# LINKER.net
KiCad netlist of a schematic drawn in Altium Designer
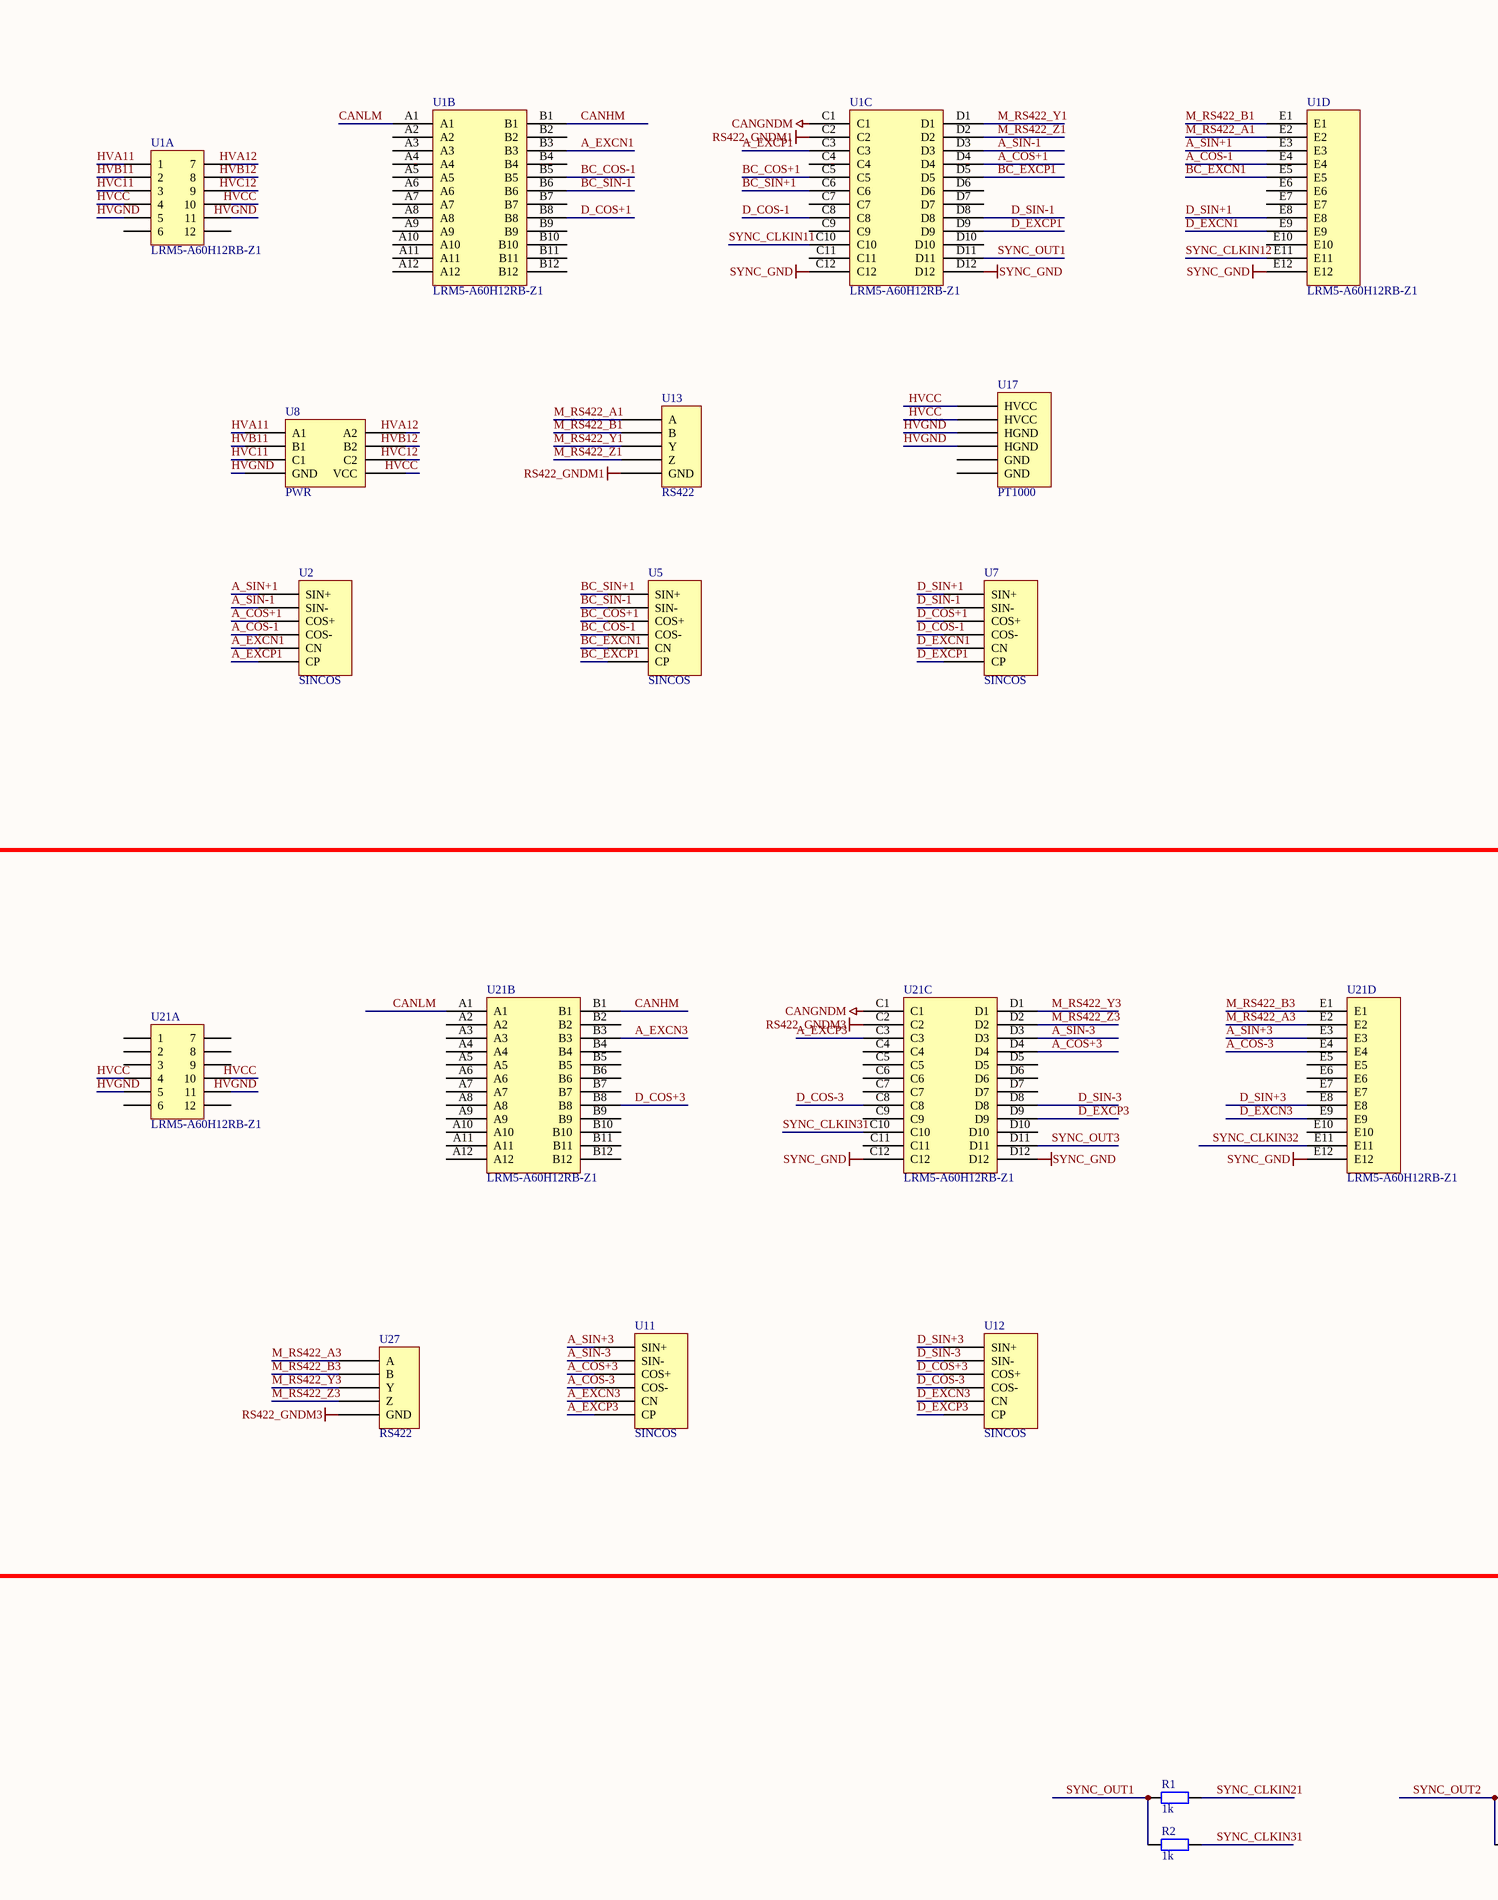
[diagram p0: LINKER.SchDoc, left]
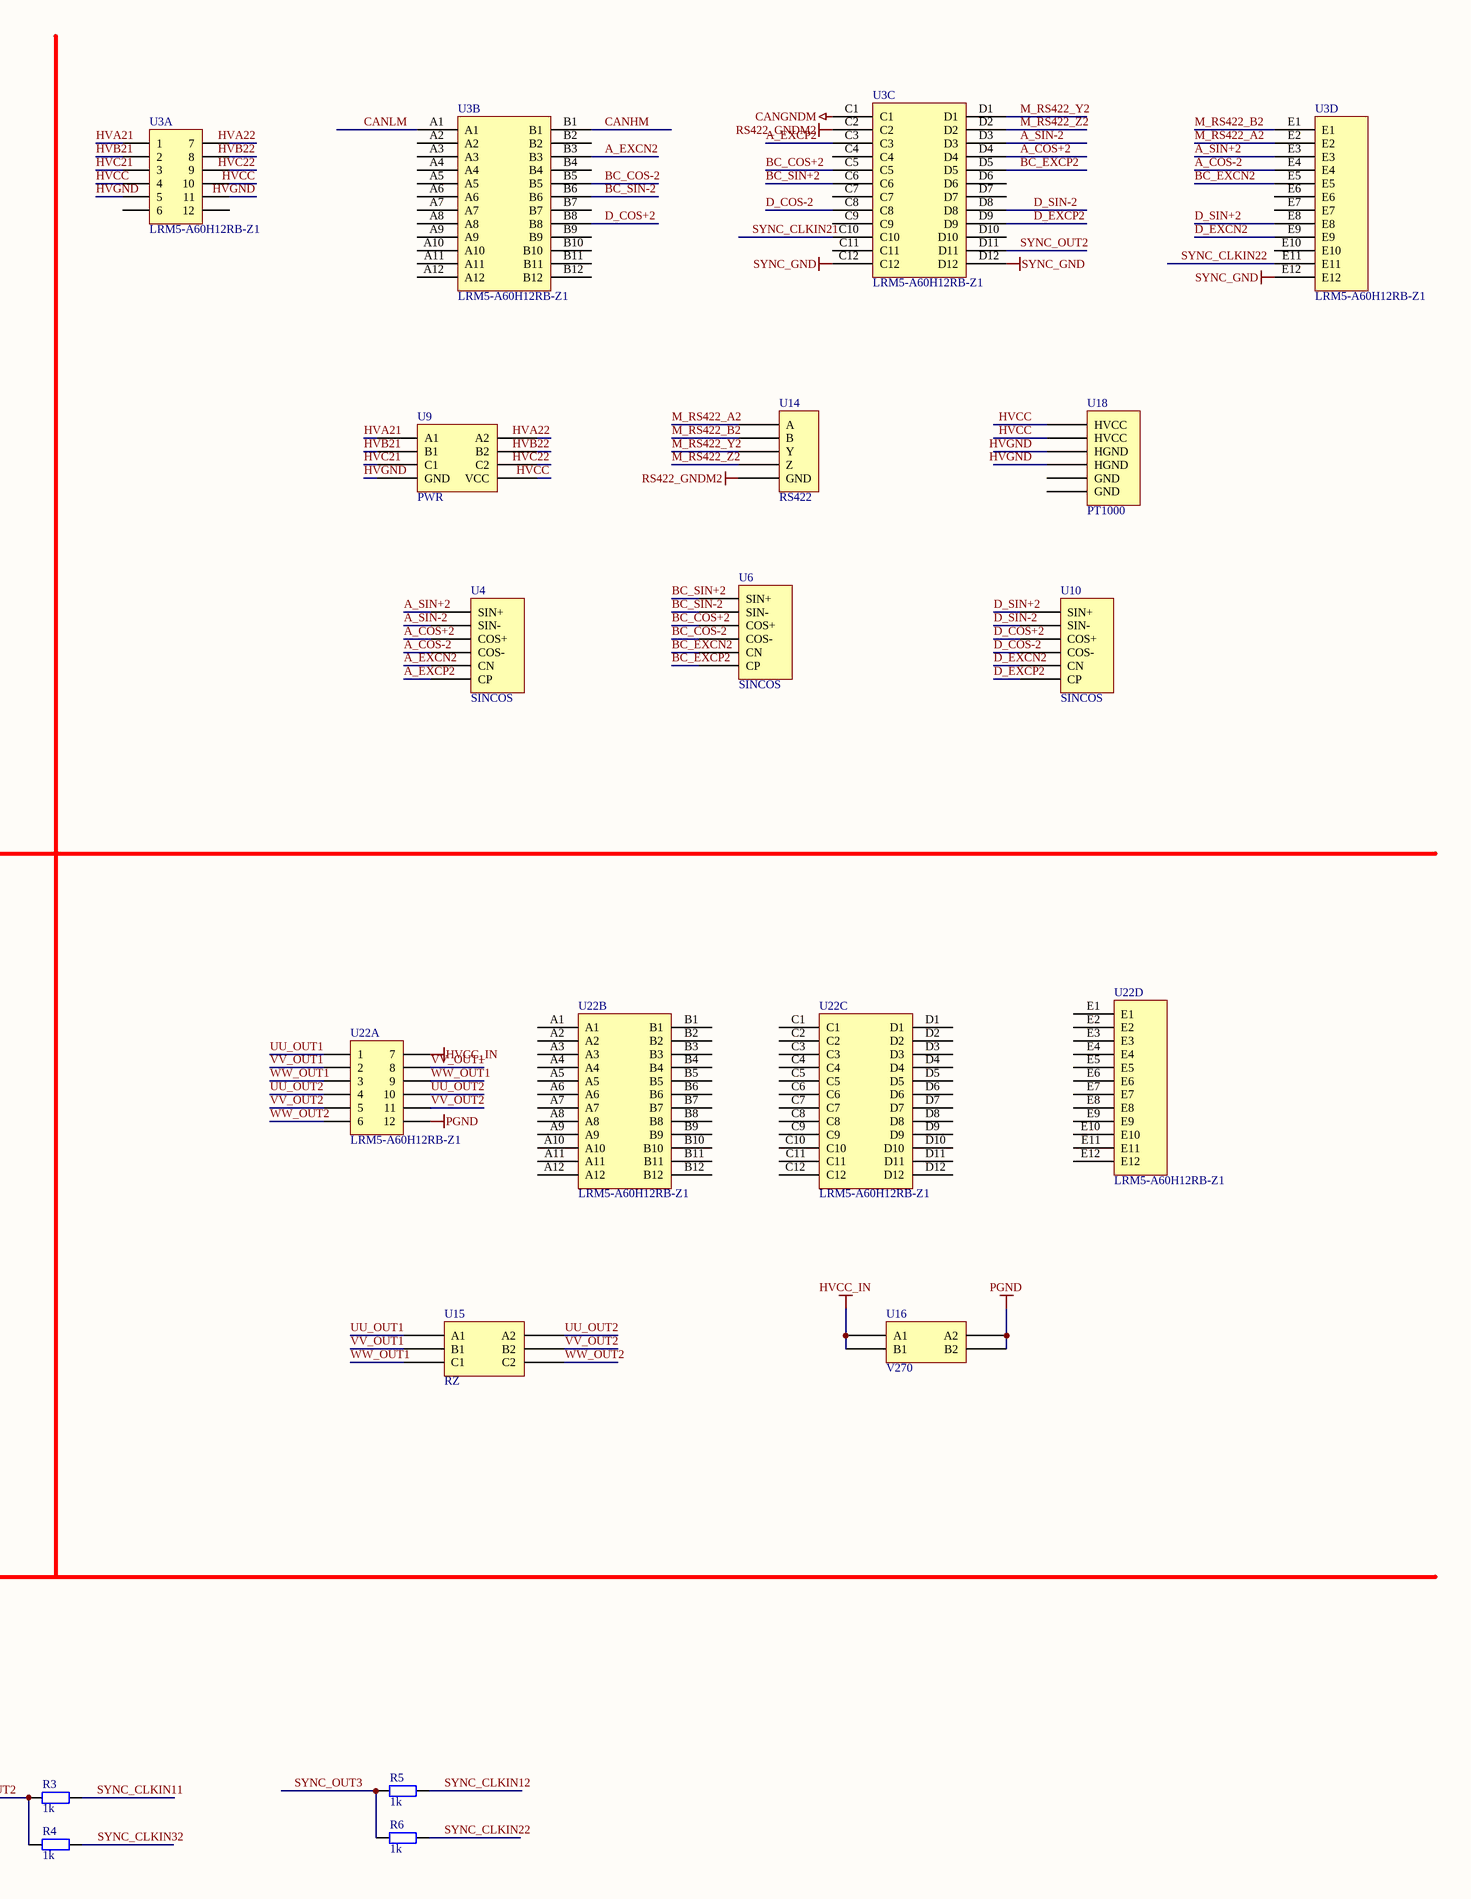
[diagram p1: LINKER.SchDoc, right]

(export (version "E")
  (design (tool "Eeschema 10.0.6"))
  (components
    (comp (ref "R1")
      (value "1k")
      (footprint "R1608-0603")
      (description "电阻器")
      (libsource (lib "电阻元件库") (part "RMK1608MB"))
    )
    (comp (ref "R2")
      (value "1k")
      (footprint "R1608-0603")
      (description "电阻器")
      (libsource (lib "电阻元件库") (part "RMK1608MB"))
    )
    (comp (ref "R3")
      (value "1k")
      (footprint "R1608-0603")
      (description "电阻器")
      (libsource (lib "电阻元件库") (part "RMK1608MB"))
    )
    (comp (ref "R4")
      (value "1k")
      (footprint "R1608-0603")
      (description "电阻器")
      (libsource (lib "电阻元件库") (part "RMK1608MB"))
    )
    (comp (ref "R5")
      (value "1k")
      (footprint "R1608-0603")
      (description "电阻器")
      (libsource (lib "电阻元件库") (part "RMK1608MB"))
    )
    (comp (ref "R6")
      (value "1k")
      (footprint "R1608-0603")
      (description "电阻器")
      (libsource (lib "电阻元件库") (part "RMK1608MB"))
    )
    (comp (ref "U1")
      (value "LRM5-A60H12RB-Z1")
      (footprint "LRM5-A60H12RB-Z1")
      (libsource (lib "Interface2") (part "MULTI_HEADER"))
    )
    (comp (ref "U2") (value "SINCOS") (footprint "SINCOS") (libsource (lib "link") (part "SINCOS")))
    (comp (ref "U3")
      (value "LRM5-A60H12RB-Z1")
      (footprint "LRM5-A60H12RB-Z1")
      (libsource (lib "Interface2") (part "MULTI_HEADER"))
    )
    (comp (ref "U4") (value "SINCOS") (footprint "SINCOS") (libsource (lib "link") (part "SINCOS")))
    (comp (ref "U5") (value "SINCOS") (footprint "SINCOS") (libsource (lib "link") (part "SINCOS")))
    (comp (ref "U6") (value "SINCOS") (footprint "SINCOS") (libsource (lib "link") (part "SINCOS")))
    (comp (ref "U7") (value "SINCOS") (footprint "SINCOS") (libsource (lib "link") (part "SINCOS")))
    (comp (ref "U8") (value "PWR") (footprint "PWR") (libsource (lib "link") (part "PWR")))
    (comp (ref "U9") (value "PWR") (footprint "PWR") (libsource (lib "link") (part "PWR")))
    (comp (ref "U10") (value "SINCOS") (footprint "SINCOS") (libsource (lib "link") (part "SINCOS")))
    (comp (ref "U11") (value "SINCOS") (footprint "SINCOS") (libsource (lib "link") (part "SINCOS")))
    (comp (ref "U12") (value "SINCOS") (footprint "SINCOS") (libsource (lib "link") (part "SINCOS")))
    (comp (ref "U13") (value "RS422") (footprint "RS422") (libsource (lib "link") (part "RS422")))
    (comp (ref "U14") (value "RS422") (footprint "RS422") (libsource (lib "link") (part "RS422")))
    (comp (ref "U15") (value "RZ") (footprint "RZ") (libsource (lib "link") (part "RZ")))
    (comp (ref "U16") (value "V270") (footprint "V270") (libsource (lib "link") (part "V270")))
    (comp (ref "U17") (value "PT1000") (footprint "PT1000") (libsource (lib "link") (part "PT1000")))
    (comp (ref "U18") (value "PT1000") (footprint "PT1000") (libsource (lib "link") (part "PT1000")))
    (comp (ref "U21")
      (value "LRM5-A60H12RB-Z1")
      (footprint "LRM5-A60H12RB-Z1")
      (libsource (lib "Interface2") (part "MULTI_HEADER"))
    )
    (comp (ref "U22")
      (value "LRM5-A60H12RB-Z1")
      (footprint "LRM5-A60H12RB-Z1")
      (libsource (lib "Interface2") (part "MULTI_HEADER"))
    )
    (comp (ref "U27") (value "RS422") (footprint "RS422") (libsource (lib "link") (part "RS422")))
  )
  (nets
    (net (code "1") (name "/A_COS+1") (class "Default")
      (node (ref "U1") (pin "D4") (pinfunction "D4_D4") (pintype "passive"))
      (node (ref "U2") (pin "3") (pinfunction "COS+_3") (pintype "passive"))
    )
    (net (code "2") (name "/A_COS+2") (class "Default")
      (node (ref "U3") (pin "D4") (pinfunction "D4_D4") (pintype "passive"))
      (node (ref "U4") (pin "3") (pinfunction "COS+_3") (pintype "passive"))
    )
    (net (code "3") (name "/A_COS+3") (class "Default")
      (node (ref "U11") (pin "3") (pinfunction "COS+_3") (pintype "passive"))
      (node (ref "U21") (pin "D4") (pinfunction "D4_D4") (pintype "passive"))
    )
    (net (code "4") (name "/A_COS-1") (class "Default")
      (node (ref "U1") (pin "E4") (pinfunction "E4_E4") (pintype "passive"))
      (node (ref "U2") (pin "4") (pinfunction "COS-_4") (pintype "passive"))
    )
    (net (code "5") (name "/A_COS-2") (class "Default")
      (node (ref "U3") (pin "E4") (pinfunction "E4_E4") (pintype "passive"))
      (node (ref "U4") (pin "4") (pinfunction "COS-_4") (pintype "passive"))
    )
    (net (code "6") (name "/A_COS-3") (class "Default")
      (node (ref "U11") (pin "4") (pinfunction "COS-_4") (pintype "passive"))
      (node (ref "U21") (pin "E4") (pinfunction "E4_E4") (pintype "passive"))
    )
    (net (code "7") (name "/A_EXCN1") (class "Default")
      (node (ref "U1") (pin "B3") (pinfunction "B3_B3") (pintype "passive"))
      (node (ref "U2") (pin "5") (pinfunction "CN_5") (pintype "passive"))
    )
    (net (code "8") (name "/A_EXCN2") (class "Default")
      (node (ref "U3") (pin "B3") (pinfunction "B3_B3") (pintype "passive"))
      (node (ref "U4") (pin "5") (pinfunction "CN_5") (pintype "passive"))
    )
    (net (code "9") (name "/A_EXCN3") (class "Default")
      (node (ref "U11") (pin "5") (pinfunction "CN_5") (pintype "passive"))
      (node (ref "U21") (pin "B3") (pinfunction "B3_B3") (pintype "passive"))
    )
    (net (code "10") (name "/A_EXCP1") (class "Default")
      (node (ref "U1") (pin "C3") (pinfunction "C3_C3") (pintype "passive"))
      (node (ref "U2") (pin "6") (pinfunction "CP_6") (pintype "passive"))
    )
    (net (code "11") (name "/A_EXCP2") (class "Default")
      (node (ref "U3") (pin "C3") (pinfunction "C3_C3") (pintype "passive"))
      (node (ref "U4") (pin "6") (pinfunction "CP_6") (pintype "passive"))
    )
    (net (code "12") (name "/A_EXCP3") (class "Default")
      (node (ref "U11") (pin "6") (pinfunction "CP_6") (pintype "passive"))
      (node (ref "U21") (pin "C3") (pinfunction "C3_C3") (pintype "passive"))
    )
    (net (code "13") (name "/A_SIN+1") (class "Default")
      (node (ref "U1") (pin "E3") (pinfunction "E3_E3") (pintype "passive"))
      (node (ref "U2") (pin "1") (pinfunction "SIN+_1") (pintype "passive"))
    )
    (net (code "14") (name "/A_SIN+2") (class "Default")
      (node (ref "U3") (pin "E3") (pinfunction "E3_E3") (pintype "passive"))
      (node (ref "U4") (pin "1") (pinfunction "SIN+_1") (pintype "passive"))
    )
    (net (code "15") (name "/A_SIN+3") (class "Default")
      (node (ref "U11") (pin "1") (pinfunction "SIN+_1") (pintype "passive"))
      (node (ref "U21") (pin "E3") (pinfunction "E3_E3") (pintype "passive"))
    )
    (net (code "16") (name "/A_SIN-1") (class "Default")
      (node (ref "U1") (pin "D3") (pinfunction "D3_D3") (pintype "passive"))
      (node (ref "U2") (pin "2") (pinfunction "SIN-_2") (pintype "passive"))
    )
    (net (code "17") (name "/A_SIN-2") (class "Default")
      (node (ref "U3") (pin "D3") (pinfunction "D3_D3") (pintype "passive"))
      (node (ref "U4") (pin "2") (pinfunction "SIN-_2") (pintype "passive"))
    )
    (net (code "18") (name "/A_SIN-3") (class "Default")
      (node (ref "U11") (pin "2") (pinfunction "SIN-_2") (pintype "passive"))
      (node (ref "U21") (pin "D3") (pinfunction "D3_D3") (pintype "passive"))
    )
    (net (code "19") (name "/BC_COS+1") (class "Default")
      (node (ref "U1") (pin "C5") (pinfunction "C5_C5") (pintype "passive"))
      (node (ref "U5") (pin "3") (pinfunction "COS+_3") (pintype "passive"))
    )
    (net (code "20") (name "/BC_COS+2") (class "Default")
      (node (ref "U3") (pin "C5") (pinfunction "C5_C5") (pintype "passive"))
      (node (ref "U6") (pin "3") (pinfunction "COS+_3") (pintype "passive"))
    )
    (net (code "21") (name "/BC_COS-1") (class "Default")
      (node (ref "U1") (pin "B5") (pinfunction "B5_B5") (pintype "passive"))
      (node (ref "U5") (pin "4") (pinfunction "COS-_4") (pintype "passive"))
    )
    (net (code "22") (name "/BC_COS-2") (class "Default")
      (node (ref "U3") (pin "B5") (pinfunction "B5_B5") (pintype "passive"))
      (node (ref "U6") (pin "4") (pinfunction "COS-_4") (pintype "passive"))
    )
    (net (code "23") (name "/BC_EXCN1") (class "Default")
      (node (ref "U1") (pin "E5") (pinfunction "E5_E5") (pintype "passive"))
      (node (ref "U5") (pin "5") (pinfunction "CN_5") (pintype "passive"))
    )
    (net (code "24") (name "/BC_EXCN2") (class "Default")
      (node (ref "U3") (pin "E5") (pinfunction "E5_E5") (pintype "passive"))
      (node (ref "U6") (pin "5") (pinfunction "CN_5") (pintype "passive"))
    )
    (net (code "25") (name "/BC_EXCP1") (class "Default")
      (node (ref "U1") (pin "D5") (pinfunction "D5_D5") (pintype "passive"))
      (node (ref "U5") (pin "6") (pinfunction "CP_6") (pintype "passive"))
    )
    (net (code "26") (name "/BC_EXCP2") (class "Default")
      (node (ref "U3") (pin "D5") (pinfunction "D5_D5") (pintype "passive"))
      (node (ref "U6") (pin "6") (pinfunction "CP_6") (pintype "passive"))
    )
    (net (code "27") (name "/BC_SIN+1") (class "Default")
      (node (ref "U1") (pin "C6") (pinfunction "C6_C6") (pintype "passive"))
      (node (ref "U5") (pin "1") (pinfunction "SIN+_1") (pintype "passive"))
    )
    (net (code "28") (name "/BC_SIN+2") (class "Default")
      (node (ref "U3") (pin "C6") (pinfunction "C6_C6") (pintype "passive"))
      (node (ref "U6") (pin "1") (pinfunction "SIN+_1") (pintype "passive"))
    )
    (net (code "29") (name "/BC_SIN-1") (class "Default")
      (node (ref "U1") (pin "B6") (pinfunction "B6_B6") (pintype "passive"))
      (node (ref "U5") (pin "2") (pinfunction "SIN-_2") (pintype "passive"))
    )
    (net (code "30") (name "/BC_SIN-2") (class "Default")
      (node (ref "U3") (pin "B6") (pinfunction "B6_B6") (pintype "passive"))
      (node (ref "U6") (pin "2") (pinfunction "SIN-_2") (pintype "passive"))
    )
    (net (code "31") (name "/CANHM") (class "Default")
      (node (ref "U1") (pin "B1") (pinfunction "B1_B1") (pintype "passive"))
      (node (ref "U21") (pin "B1") (pinfunction "B1_B1") (pintype "passive"))
      (node (ref "U3") (pin "B1") (pinfunction "B1_B1") (pintype "passive"))
    )
    (net (code "32") (name "/CANLM") (class "Default")
      (node (ref "U1") (pin "A1") (pinfunction "A1_A1") (pintype "passive"))
      (node (ref "U21") (pin "A1") (pinfunction "A1_A1") (pintype "passive"))
      (node (ref "U3") (pin "A1") (pinfunction "A1_A1") (pintype "passive"))
    )
    (net (code "33") (name "/D_COS+1") (class "Default")
      (node (ref "U1") (pin "B8") (pinfunction "B8_B8") (pintype "passive"))
      (node (ref "U7") (pin "3") (pinfunction "COS+_3") (pintype "passive"))
    )
    (net (code "34") (name "/D_COS+2") (class "Default")
      (node (ref "U10") (pin "3") (pinfunction "COS+_3") (pintype "passive"))
      (node (ref "U3") (pin "B8") (pinfunction "B8_B8") (pintype "passive"))
    )
    (net (code "35") (name "/D_COS+3") (class "Default")
      (node (ref "U12") (pin "3") (pinfunction "COS+_3") (pintype "passive"))
      (node (ref "U21") (pin "B8") (pinfunction "B8_B8") (pintype "passive"))
    )
    (net (code "36") (name "/D_COS-1") (class "Default")
      (node (ref "U1") (pin "C8") (pinfunction "C8_C8") (pintype "passive"))
      (node (ref "U7") (pin "4") (pinfunction "COS-_4") (pintype "passive"))
    )
    (net (code "37") (name "/D_COS-2") (class "Default")
      (node (ref "U10") (pin "4") (pinfunction "COS-_4") (pintype "passive"))
      (node (ref "U3") (pin "C8") (pinfunction "C8_C8") (pintype "passive"))
    )
    (net (code "38") (name "/D_COS-3") (class "Default")
      (node (ref "U12") (pin "4") (pinfunction "COS-_4") (pintype "passive"))
      (node (ref "U21") (pin "C8") (pinfunction "C8_C8") (pintype "passive"))
    )
    (net (code "39") (name "/D_EXCN1") (class "Default")
      (node (ref "U1") (pin "E9") (pinfunction "E9_E9") (pintype "passive"))
      (node (ref "U7") (pin "5") (pinfunction "CN_5") (pintype "passive"))
    )
    (net (code "40") (name "/D_EXCN2") (class "Default")
      (node (ref "U10") (pin "5") (pinfunction "CN_5") (pintype "passive"))
      (node (ref "U3") (pin "E9") (pinfunction "E9_E9") (pintype "passive"))
    )
    (net (code "41") (name "/D_EXCN3") (class "Default")
      (node (ref "U12") (pin "5") (pinfunction "CN_5") (pintype "passive"))
      (node (ref "U21") (pin "E9") (pinfunction "E9_E9") (pintype "passive"))
    )
    (net (code "42") (name "/D_EXCP1") (class "Default")
      (node (ref "U1") (pin "D9") (pinfunction "D9_D9") (pintype "passive"))
      (node (ref "U7") (pin "6") (pinfunction "CP_6") (pintype "passive"))
    )
    (net (code "43") (name "/D_EXCP2") (class "Default")
      (node (ref "U10") (pin "6") (pinfunction "CP_6") (pintype "passive"))
      (node (ref "U3") (pin "D9") (pinfunction "D9_D9") (pintype "passive"))
    )
    (net (code "44") (name "/D_EXCP3") (class "Default")
      (node (ref "U12") (pin "6") (pinfunction "CP_6") (pintype "passive"))
      (node (ref "U21") (pin "D9") (pinfunction "D9_D9") (pintype "passive"))
    )
    (net (code "45") (name "/D_SIN+1") (class "Default")
      (node (ref "U1") (pin "E8") (pinfunction "E8_E8") (pintype "passive"))
      (node (ref "U7") (pin "1") (pinfunction "SIN+_1") (pintype "passive"))
    )
    (net (code "46") (name "/D_SIN+2") (class "Default")
      (node (ref "U10") (pin "1") (pinfunction "SIN+_1") (pintype "passive"))
      (node (ref "U3") (pin "E8") (pinfunction "E8_E8") (pintype "passive"))
    )
    (net (code "47") (name "/D_SIN+3") (class "Default")
      (node (ref "U12") (pin "1") (pinfunction "SIN+_1") (pintype "passive"))
      (node (ref "U21") (pin "E8") (pinfunction "E8_E8") (pintype "passive"))
    )
    (net (code "48") (name "/D_SIN-1") (class "Default")
      (node (ref "U1") (pin "D8") (pinfunction "D8_D8") (pintype "passive"))
      (node (ref "U7") (pin "2") (pinfunction "SIN-_2") (pintype "passive"))
    )
    (net (code "49") (name "/D_SIN-2") (class "Default")
      (node (ref "U10") (pin "2") (pinfunction "SIN-_2") (pintype "passive"))
      (node (ref "U3") (pin "D8") (pinfunction "D8_D8") (pintype "passive"))
    )
    (net (code "50") (name "/D_SIN-3") (class "Default")
      (node (ref "U12") (pin "2") (pinfunction "SIN-_2") (pintype "passive"))
      (node (ref "U21") (pin "D8") (pinfunction "D8_D8") (pintype "passive"))
    )
    (net (code "51") (name "/HVA11") (class "Default")
      (node (ref "U1") (pin "1") (pinfunction "1_1") (pintype "passive"))
      (node (ref "U8") (pin "1") (pinfunction "A1_1") (pintype "passive"))
    )
    (net (code "52") (name "/HVA12") (class "Default")
      (node (ref "U1") (pin "7") (pinfunction "7_7") (pintype "passive"))
      (node (ref "U8") (pin "4") (pinfunction "A2_4") (pintype "passive"))
    )
    (net (code "53") (name "/HVA21") (class "Default")
      (node (ref "U3") (pin "1") (pinfunction "1_1") (pintype "passive"))
      (node (ref "U9") (pin "1") (pinfunction "A1_1") (pintype "passive"))
    )
    (net (code "54") (name "/HVA22") (class "Default")
      (node (ref "U3") (pin "7") (pinfunction "7_7") (pintype "passive"))
      (node (ref "U9") (pin "4") (pinfunction "A2_4") (pintype "passive"))
    )
    (net (code "55") (name "/HVB11") (class "Default")
      (node (ref "U1") (pin "2") (pinfunction "2_2") (pintype "passive"))
      (node (ref "U8") (pin "2") (pinfunction "B1_2") (pintype "passive"))
    )
    (net (code "56") (name "/HVB12") (class "Default")
      (node (ref "U1") (pin "8") (pinfunction "8_8") (pintype "passive"))
      (node (ref "U8") (pin "5") (pinfunction "B2_5") (pintype "passive"))
    )
    (net (code "57") (name "/HVB21") (class "Default")
      (node (ref "U3") (pin "2") (pinfunction "2_2") (pintype "passive"))
      (node (ref "U9") (pin "2") (pinfunction "B1_2") (pintype "passive"))
    )
    (net (code "58") (name "/HVB22") (class "Default")
      (node (ref "U3") (pin "8") (pinfunction "8_8") (pintype "passive"))
      (node (ref "U9") (pin "5") (pinfunction "B2_5") (pintype "passive"))
    )
    (net (code "59") (name "/HVC11") (class "Default")
      (node (ref "U1") (pin "3") (pinfunction "3_3") (pintype "passive"))
      (node (ref "U8") (pin "3") (pinfunction "C1_3") (pintype "passive"))
    )
    (net (code "60") (name "/HVC12") (class "Default")
      (node (ref "U1") (pin "9") (pinfunction "9_9") (pintype "passive"))
      (node (ref "U8") (pin "6") (pinfunction "C2_6") (pintype "passive"))
    )
    (net (code "61") (name "/HVC21") (class "Default")
      (node (ref "U3") (pin "3") (pinfunction "3_3") (pintype "passive"))
      (node (ref "U9") (pin "3") (pinfunction "C1_3") (pintype "passive"))
    )
    (net (code "62") (name "/HVC22") (class "Default")
      (node (ref "U3") (pin "9") (pinfunction "9_9") (pintype "passive"))
      (node (ref "U9") (pin "6") (pinfunction "C2_6") (pintype "passive"))
    )
    (net (code "63") (name "/HVCC") (class "Default")
      (node (ref "U1") (pin "10") (pinfunction "10_10") (pintype "passive"))
      (node (ref "U1") (pin "4") (pinfunction "4_4") (pintype "passive"))
      (node (ref "U17") (pin "1") (pinfunction "HVCC_1") (pintype "passive"))
      (node (ref "U17") (pin "2") (pinfunction "HVCC_2") (pintype "passive"))
      (node (ref "U18") (pin "1") (pinfunction "HVCC_1") (pintype "passive"))
      (node (ref "U18") (pin "2") (pinfunction "HVCC_2") (pintype "passive"))
      (node (ref "U21") (pin "10") (pinfunction "10_10") (pintype "passive"))
      (node (ref "U21") (pin "4") (pinfunction "4_4") (pintype "passive"))
      (node (ref "U3") (pin "10") (pinfunction "10_10") (pintype "passive"))
      (node (ref "U3") (pin "4") (pinfunction "4_4") (pintype "passive"))
      (node (ref "U8") (pin "8") (pinfunction "VCC_8") (pintype "passive"))
      (node (ref "U9") (pin "8") (pinfunction "VCC_8") (pintype "passive"))
    )
    (net (code "64") (name "/HVGND") (class "Default")
      (node (ref "U1") (pin "11") (pinfunction "11_11") (pintype "passive"))
      (node (ref "U1") (pin "5") (pinfunction "5_5") (pintype "passive"))
      (node (ref "U17") (pin "3") (pinfunction "HGND_3") (pintype "passive"))
      (node (ref "U17") (pin "4") (pinfunction "HGND_4") (pintype "passive"))
      (node (ref "U18") (pin "3") (pinfunction "HGND_3") (pintype "passive"))
      (node (ref "U18") (pin "4") (pinfunction "HGND_4") (pintype "passive"))
      (node (ref "U21") (pin "11") (pinfunction "11_11") (pintype "passive"))
      (node (ref "U21") (pin "5") (pinfunction "5_5") (pintype "passive"))
      (node (ref "U3") (pin "11") (pinfunction "11_11") (pintype "passive"))
      (node (ref "U3") (pin "5") (pinfunction "5_5") (pintype "passive"))
      (node (ref "U8") (pin "7") (pinfunction "GND_7") (pintype "passive"))
      (node (ref "U9") (pin "7") (pinfunction "GND_7") (pintype "passive"))
    )
    (net (code "65") (name "/M_RS422_A1") (class "Default")
      (node (ref "U1") (pin "E2") (pinfunction "E2_E2") (pintype "passive"))
      (node (ref "U13") (pin "1") (pinfunction "A_1") (pintype "passive"))
    )
    (net (code "66") (name "/M_RS422_A2") (class "Default")
      (node (ref "U14") (pin "1") (pinfunction "A_1") (pintype "passive"))
      (node (ref "U3") (pin "E2") (pinfunction "E2_E2") (pintype "passive"))
    )
    (net (code "67") (name "/M_RS422_A3") (class "Default")
      (node (ref "U21") (pin "E2") (pinfunction "E2_E2") (pintype "passive"))
      (node (ref "U27") (pin "1") (pinfunction "A_1") (pintype "passive"))
    )
    (net (code "68") (name "/M_RS422_B1") (class "Default")
      (node (ref "U1") (pin "E1") (pinfunction "E1_E1") (pintype "passive"))
      (node (ref "U13") (pin "2") (pinfunction "B_2") (pintype "passive"))
    )
    (net (code "69") (name "/M_RS422_B2") (class "Default")
      (node (ref "U14") (pin "2") (pinfunction "B_2") (pintype "passive"))
      (node (ref "U3") (pin "E1") (pinfunction "E1_E1") (pintype "passive"))
    )
    (net (code "70") (name "/M_RS422_B3") (class "Default")
      (node (ref "U21") (pin "E1") (pinfunction "E1_E1") (pintype "passive"))
      (node (ref "U27") (pin "2") (pinfunction "B_2") (pintype "passive"))
    )
    (net (code "71") (name "/M_RS422_Y1") (class "Default")
      (node (ref "U1") (pin "D1") (pinfunction "D1_D1") (pintype "passive"))
      (node (ref "U13") (pin "3") (pinfunction "Y_3") (pintype "passive"))
    )
    (net (code "72") (name "/M_RS422_Y2") (class "Default")
      (node (ref "U14") (pin "3") (pinfunction "Y_3") (pintype "passive"))
      (node (ref "U3") (pin "D1") (pinfunction "D1_D1") (pintype "passive"))
    )
    (net (code "73") (name "/M_RS422_Y3") (class "Default")
      (node (ref "U21") (pin "D1") (pinfunction "D1_D1") (pintype "passive"))
      (node (ref "U27") (pin "3") (pinfunction "Y_3") (pintype "passive"))
    )
    (net (code "74") (name "/M_RS422_Z1") (class "Default")
      (node (ref "U1") (pin "D2") (pinfunction "D2_D2") (pintype "passive"))
      (node (ref "U13") (pin "4") (pinfunction "Z_4") (pintype "passive"))
    )
    (net (code "75") (name "/M_RS422_Z2") (class "Default")
      (node (ref "U14") (pin "4") (pinfunction "Z_4") (pintype "passive"))
      (node (ref "U3") (pin "D2") (pinfunction "D2_D2") (pintype "passive"))
    )
    (net (code "76") (name "/M_RS422_Z3") (class "Default")
      (node (ref "U21") (pin "D2") (pinfunction "D2_D2") (pintype "passive"))
      (node (ref "U27") (pin "4") (pinfunction "Z_4") (pintype "passive"))
    )
    (net (code "77") (name "/SYNC_CLKIN11") (class "Default")
      (node (ref "R3") (pin "2") (pinfunction "2_2") (pintype "passive"))
      (node (ref "U1") (pin "C10") (pinfunction "C10_C10") (pintype "passive"))
    )
    (net (code "78") (name "/SYNC_CLKIN12") (class "Default")
      (node (ref "R5") (pin "2") (pinfunction "2_2") (pintype "passive"))
      (node (ref "U1") (pin "E11") (pinfunction "E11_E11") (pintype "passive"))
    )
    (net (code "79") (name "/SYNC_CLKIN21") (class "Default")
      (node (ref "R1") (pin "2") (pinfunction "2_2") (pintype "passive"))
      (node (ref "U3") (pin "C10") (pinfunction "C10_C10") (pintype "passive"))
    )
    (net (code "80") (name "/SYNC_CLKIN22") (class "Default")
      (node (ref "R6") (pin "2") (pinfunction "2_2") (pintype "passive"))
      (node (ref "U3") (pin "E11") (pinfunction "E11_E11") (pintype "passive"))
    )
    (net (code "81") (name "/SYNC_CLKIN31") (class "Default")
      (node (ref "R2") (pin "2") (pinfunction "2_2") (pintype "passive"))
      (node (ref "U21") (pin "C10") (pinfunction "C10_C10") (pintype "passive"))
    )
    (net (code "82") (name "/SYNC_CLKIN32") (class "Default")
      (node (ref "R4") (pin "2") (pinfunction "2_2") (pintype "passive"))
      (node (ref "U21") (pin "E11") (pinfunction "E11_E11") (pintype "passive"))
    )
    (net (code "83") (name "/SYNC_OUT1") (class "Default")
      (node (ref "R1") (pin "1") (pinfunction "1_1") (pintype "passive"))
      (node (ref "R2") (pin "1") (pinfunction "1_1") (pintype "passive"))
      (node (ref "U1") (pin "D11") (pinfunction "D11_D11") (pintype "passive"))
    )
    (net (code "84") (name "/SYNC_OUT2") (class "Default")
      (node (ref "R3") (pin "1") (pinfunction "1_1") (pintype "passive"))
      (node (ref "R4") (pin "1") (pinfunction "1_1") (pintype "passive"))
      (node (ref "U3") (pin "D11") (pinfunction "D11_D11") (pintype "passive"))
    )
    (net (code "85") (name "/SYNC_OUT3") (class "Default")
      (node (ref "R5") (pin "1") (pinfunction "1_1") (pintype "passive"))
      (node (ref "R6") (pin "1") (pinfunction "1_1") (pintype "passive"))
      (node (ref "U21") (pin "D11") (pinfunction "D11_D11") (pintype "passive"))
    )
    (net (code "86") (name "/UU_OUT1") (class "Default")
      (node (ref "U15") (pin "1") (pinfunction "A1_1") (pintype "passive"))
      (node (ref "U22") (pin "1") (pinfunction "1_1") (pintype "passive"))
    )
    (net (code "87") (name "/UU_OUT2") (class "Default")
      (node (ref "U15") (pin "4") (pinfunction "A2_4") (pintype "passive"))
      (node (ref "U22") (pin "10") (pinfunction "10_10") (pintype "passive"))
      (node (ref "U22") (pin "4") (pinfunction "4_4") (pintype "passive"))
    )
    (net (code "88") (name "/VV_OUT1") (class "Default")
      (node (ref "U15") (pin "2") (pinfunction "B1_2") (pintype "passive"))
      (node (ref "U22") (pin "2") (pinfunction "2_2") (pintype "passive"))
      (node (ref "U22") (pin "8") (pinfunction "8_8") (pintype "passive"))
    )
    (net (code "89") (name "/VV_OUT2") (class "Default")
      (node (ref "U15") (pin "5") (pinfunction "B2_5") (pintype "passive"))
      (node (ref "U22") (pin "11") (pinfunction "11_11") (pintype "passive"))
      (node (ref "U22") (pin "5") (pinfunction "5_5") (pintype "passive"))
    )
    (net (code "90") (name "/WW_OUT1") (class "Default")
      (node (ref "U15") (pin "3") (pinfunction "C1_3") (pintype "passive"))
      (node (ref "U22") (pin "3") (pinfunction "3_3") (pintype "passive"))
      (node (ref "U22") (pin "9") (pinfunction "9_9") (pintype "passive"))
    )
    (net (code "91") (name "/WW_OUT2") (class "Default")
      (node (ref "U15") (pin "6") (pinfunction "C2_6") (pintype "passive"))
      (node (ref "U22") (pin "6") (pinfunction "6_6") (pintype "passive"))
    )
    (net (code "92") (name "CANGNDM") (class "Default")
      (node (ref "U1") (pin "C1") (pinfunction "C1_C1") (pintype "passive"))
      (node (ref "U21") (pin "C1") (pinfunction "C1_C1") (pintype "passive"))
      (node (ref "U3") (pin "C1") (pinfunction "C1_C1") (pintype "passive"))
    )
    (net (code "93") (name "HVCC_IN") (class "Default")
      (node (ref "U16") (pin "1") (pinfunction "A1_1") (pintype "passive"))
      (node (ref "U16") (pin "2") (pinfunction "B1_2") (pintype "passive"))
      (node (ref "U22") (pin "7") (pinfunction "7_7") (pintype "passive"))
    )
    (net (code "94") (name "PGND") (class "Default")
      (node (ref "U16") (pin "3") (pinfunction "A2_3") (pintype "passive"))
      (node (ref "U16") (pin "4") (pinfunction "B2_4") (pintype "passive"))
      (node (ref "U22") (pin "12") (pinfunction "12_12") (pintype "passive"))
    )
    (net (code "95") (name "RS422_GNDM1") (class "Default")
      (node (ref "U1") (pin "C2") (pinfunction "C2_C2") (pintype "passive"))
      (node (ref "U13") (pin "5") (pinfunction "GND_5") (pintype "passive"))
    )
    (net (code "96") (name "RS422_GNDM2") (class "Default")
      (node (ref "U14") (pin "5") (pinfunction "GND_5") (pintype "passive"))
      (node (ref "U3") (pin "C2") (pinfunction "C2_C2") (pintype "passive"))
    )
    (net (code "97") (name "RS422_GNDM3") (class "Default")
      (node (ref "U21") (pin "C2") (pinfunction "C2_C2") (pintype "passive"))
      (node (ref "U27") (pin "5") (pinfunction "GND_5") (pintype "passive"))
    )
    (net (code "98") (name "SYNC_GND") (class "Default")
      (node (ref "U1") (pin "C12") (pinfunction "C12_C12") (pintype "passive"))
      (node (ref "U1") (pin "D12") (pinfunction "D12_D12") (pintype "passive"))
      (node (ref "U1") (pin "E12") (pinfunction "E12_E12") (pintype "passive"))
      (node (ref "U21") (pin "C12") (pinfunction "C12_C12") (pintype "passive"))
      (node (ref "U21") (pin "D12") (pinfunction "D12_D12") (pintype "passive"))
      (node (ref "U21") (pin "E12") (pinfunction "E12_E12") (pintype "passive"))
      (node (ref "U3") (pin "C12") (pinfunction "C12_C12") (pintype "passive"))
      (node (ref "U3") (pin "D12") (pinfunction "D12_D12") (pintype "passive"))
      (node (ref "U3") (pin "E12") (pinfunction "E12_E12") (pintype "passive"))
    )
    (net (code "99") (name "unconnected-(U1-Pad6)") (class "Default")
      (node (ref "U1") (pin "6") (pinfunction "6_6") (pintype "passive"))
    )
    (net (code "100") (name "unconnected-(U1-Pad12)") (class "Default")
      (node (ref "U1") (pin "12") (pinfunction "12_12") (pintype "passive"))
    )
    (net (code "101") (name "unconnected-(U1-PadA2)") (class "Default")
      (node (ref "U1") (pin "A2") (pinfunction "A2_A2") (pintype "passive"))
    )
    (net (code "102") (name "unconnected-(U1-PadA3)") (class "Default")
      (node (ref "U1") (pin "A3") (pinfunction "A3_A3") (pintype "passive"))
    )
    (net (code "103") (name "unconnected-(U1-PadA4)") (class "Default")
      (node (ref "U1") (pin "A4") (pinfunction "A4_A4") (pintype "passive"))
    )
    (net (code "104") (name "unconnected-(U1-PadA5)") (class "Default")
      (node (ref "U1") (pin "A5") (pinfunction "A5_A5") (pintype "passive"))
    )
    (net (code "105") (name "unconnected-(U1-PadA6)") (class "Default")
      (node (ref "U1") (pin "A6") (pinfunction "A6_A6") (pintype "passive"))
    )
    (net (code "106") (name "unconnected-(U1-PadA7)") (class "Default")
      (node (ref "U1") (pin "A7") (pinfunction "A7_A7") (pintype "passive"))
    )
    (net (code "107") (name "unconnected-(U1-PadA8)") (class "Default")
      (node (ref "U1") (pin "A8") (pinfunction "A8_A8") (pintype "passive"))
    )
    (net (code "108") (name "unconnected-(U1-PadA9)") (class "Default")
      (node (ref "U1") (pin "A9") (pinfunction "A9_A9") (pintype "passive"))
    )
    (net (code "109") (name "unconnected-(U1-PadA10)") (class "Default")
      (node (ref "U1") (pin "A10") (pinfunction "A10_A10") (pintype "passive"))
    )
    (net (code "110") (name "unconnected-(U1-PadA11)") (class "Default")
      (node (ref "U1") (pin "A11") (pinfunction "A11_A11") (pintype "passive"))
    )
    (net (code "111") (name "unconnected-(U1-PadA12)") (class "Default")
      (node (ref "U1") (pin "A12") (pinfunction "A12_A12") (pintype "passive"))
    )
    (net (code "112") (name "unconnected-(U1-PadB2)") (class "Default")
      (node (ref "U1") (pin "B2") (pinfunction "B2_B2") (pintype "passive"))
    )
    (net (code "113") (name "unconnected-(U1-PadB4)") (class "Default")
      (node (ref "U1") (pin "B4") (pinfunction "B4_B4") (pintype "passive"))
    )
    (net (code "114") (name "unconnected-(U1-PadB7)") (class "Default")
      (node (ref "U1") (pin "B7") (pinfunction "B7_B7") (pintype "passive"))
    )
    (net (code "115") (name "unconnected-(U1-PadB9)") (class "Default")
      (node (ref "U1") (pin "B9") (pinfunction "B9_B9") (pintype "passive"))
    )
    (net (code "116") (name "unconnected-(U1-PadB10)") (class "Default")
      (node (ref "U1") (pin "B10") (pinfunction "B10_B10") (pintype "passive"))
    )
    (net (code "117") (name "unconnected-(U1-PadB11)") (class "Default")
      (node (ref "U1") (pin "B11") (pinfunction "B11_B11") (pintype "passive"))
    )
    (net (code "118") (name "unconnected-(U1-PadB12)") (class "Default")
      (node (ref "U1") (pin "B12") (pinfunction "B12_B12") (pintype "passive"))
    )
    (net (code "119") (name "unconnected-(U1-PadC4)") (class "Default")
      (node (ref "U1") (pin "C4") (pinfunction "C4_C4") (pintype "passive"))
    )
    (net (code "120") (name "unconnected-(U1-PadC7)") (class "Default")
      (node (ref "U1") (pin "C7") (pinfunction "C7_C7") (pintype "passive"))
    )
    (net (code "121") (name "unconnected-(U1-PadC9)") (class "Default")
      (node (ref "U1") (pin "C9") (pinfunction "C9_C9") (pintype "passive"))
    )
    (net (code "122") (name "unconnected-(U1-PadC11)") (class "Default")
      (node (ref "U1") (pin "C11") (pinfunction "C11_C11") (pintype "passive"))
    )
    (net (code "123") (name "unconnected-(U1-PadD6)") (class "Default")
      (node (ref "U1") (pin "D6") (pinfunction "D6_D6") (pintype "passive"))
    )
    (net (code "124") (name "unconnected-(U1-PadD7)") (class "Default")
      (node (ref "U1") (pin "D7") (pinfunction "D7_D7") (pintype "passive"))
    )
    (net (code "125") (name "unconnected-(U1-PadD10)") (class "Default")
      (node (ref "U1") (pin "D10") (pinfunction "D10_D10") (pintype "passive"))
    )
    (net (code "126") (name "unconnected-(U1-PadE6)") (class "Default")
      (node (ref "U1") (pin "E6") (pinfunction "E6_E6") (pintype "passive"))
    )
    (net (code "127") (name "unconnected-(U1-PadE7)") (class "Default")
      (node (ref "U1") (pin "E7") (pinfunction "E7_E7") (pintype "passive"))
    )
    (net (code "128") (name "unconnected-(U1-PadE10)") (class "Default")
      (node (ref "U1") (pin "E10") (pinfunction "E10_E10") (pintype "passive"))
    )
    (net (code "129") (name "unconnected-(U3-Pad6)") (class "Default")
      (node (ref "U3") (pin "6") (pinfunction "6_6") (pintype "passive"))
    )
    (net (code "130") (name "unconnected-(U3-Pad12)") (class "Default")
      (node (ref "U3") (pin "12") (pinfunction "12_12") (pintype "passive"))
    )
    (net (code "131") (name "unconnected-(U3-PadA2)") (class "Default")
      (node (ref "U3") (pin "A2") (pinfunction "A2_A2") (pintype "passive"))
    )
    (net (code "132") (name "unconnected-(U3-PadA3)") (class "Default")
      (node (ref "U3") (pin "A3") (pinfunction "A3_A3") (pintype "passive"))
    )
    (net (code "133") (name "unconnected-(U3-PadA4)") (class "Default")
      (node (ref "U3") (pin "A4") (pinfunction "A4_A4") (pintype "passive"))
    )
    (net (code "134") (name "unconnected-(U3-PadA5)") (class "Default")
      (node (ref "U3") (pin "A5") (pinfunction "A5_A5") (pintype "passive"))
    )
    (net (code "135") (name "unconnected-(U3-PadA6)") (class "Default")
      (node (ref "U3") (pin "A6") (pinfunction "A6_A6") (pintype "passive"))
    )
    (net (code "136") (name "unconnected-(U3-PadA7)") (class "Default")
      (node (ref "U3") (pin "A7") (pinfunction "A7_A7") (pintype "passive"))
    )
    (net (code "137") (name "unconnected-(U3-PadA8)") (class "Default")
      (node (ref "U3") (pin "A8") (pinfunction "A8_A8") (pintype "passive"))
    )
    (net (code "138") (name "unconnected-(U3-PadA9)") (class "Default")
      (node (ref "U3") (pin "A9") (pinfunction "A9_A9") (pintype "passive"))
    )
    (net (code "139") (name "unconnected-(U3-PadA10)") (class "Default")
      (node (ref "U3") (pin "A10") (pinfunction "A10_A10") (pintype "passive"))
    )
    (net (code "140") (name "unconnected-(U3-PadA11)") (class "Default")
      (node (ref "U3") (pin "A11") (pinfunction "A11_A11") (pintype "passive"))
    )
    (net (code "141") (name "unconnected-(U3-PadA12)") (class "Default")
      (node (ref "U3") (pin "A12") (pinfunction "A12_A12") (pintype "passive"))
    )
    (net (code "142") (name "unconnected-(U3-PadB2)") (class "Default")
      (node (ref "U3") (pin "B2") (pinfunction "B2_B2") (pintype "passive"))
    )
    (net (code "143") (name "unconnected-(U3-PadB4)") (class "Default")
      (node (ref "U3") (pin "B4") (pinfunction "B4_B4") (pintype "passive"))
    )
    (net (code "144") (name "unconnected-(U3-PadB7)") (class "Default")
      (node (ref "U3") (pin "B7") (pinfunction "B7_B7") (pintype "passive"))
    )
    (net (code "145") (name "unconnected-(U3-PadB9)") (class "Default")
      (node (ref "U3") (pin "B9") (pinfunction "B9_B9") (pintype "passive"))
    )
    (net (code "146") (name "unconnected-(U3-PadB10)") (class "Default")
      (node (ref "U3") (pin "B10") (pinfunction "B10_B10") (pintype "passive"))
    )
    (net (code "147") (name "unconnected-(U3-PadB11)") (class "Default")
      (node (ref "U3") (pin "B11") (pinfunction "B11_B11") (pintype "passive"))
    )
    (net (code "148") (name "unconnected-(U3-PadB12)") (class "Default")
      (node (ref "U3") (pin "B12") (pinfunction "B12_B12") (pintype "passive"))
    )
    (net (code "149") (name "unconnected-(U3-PadC4)") (class "Default")
      (node (ref "U3") (pin "C4") (pinfunction "C4_C4") (pintype "passive"))
    )
    (net (code "150") (name "unconnected-(U3-PadC7)") (class "Default")
      (node (ref "U3") (pin "C7") (pinfunction "C7_C7") (pintype "passive"))
    )
    (net (code "151") (name "unconnected-(U3-PadC9)") (class "Default")
      (node (ref "U3") (pin "C9") (pinfunction "C9_C9") (pintype "passive"))
    )
    (net (code "152") (name "unconnected-(U3-PadC11)") (class "Default")
      (node (ref "U3") (pin "C11") (pinfunction "C11_C11") (pintype "passive"))
    )
    (net (code "153") (name "unconnected-(U3-PadD6)") (class "Default")
      (node (ref "U3") (pin "D6") (pinfunction "D6_D6") (pintype "passive"))
    )
    (net (code "154") (name "unconnected-(U3-PadD7)") (class "Default")
      (node (ref "U3") (pin "D7") (pinfunction "D7_D7") (pintype "passive"))
    )
    (net (code "155") (name "unconnected-(U3-PadD10)") (class "Default")
      (node (ref "U3") (pin "D10") (pinfunction "D10_D10") (pintype "passive"))
    )
    (net (code "156") (name "unconnected-(U3-PadE6)") (class "Default")
      (node (ref "U3") (pin "E6") (pinfunction "E6_E6") (pintype "passive"))
    )
    (net (code "157") (name "unconnected-(U3-PadE7)") (class "Default")
      (node (ref "U3") (pin "E7") (pinfunction "E7_E7") (pintype "passive"))
    )
    (net (code "158") (name "unconnected-(U3-PadE10)") (class "Default")
      (node (ref "U3") (pin "E10") (pinfunction "E10_E10") (pintype "passive"))
    )
    (net (code "159") (name "unconnected-(U17-GND-Pad5)") (class "Default")
      (node (ref "U17") (pin "5") (pinfunction "GND_5") (pintype "passive"))
    )
    (net (code "160") (name "unconnected-(U17-GND-Pad6)") (class "Default")
      (node (ref "U17") (pin "6") (pinfunction "GND_6") (pintype "passive"))
    )
    (net (code "161") (name "unconnected-(U18-GND-Pad5)") (class "Default")
      (node (ref "U18") (pin "5") (pinfunction "GND_5") (pintype "passive"))
    )
    (net (code "162") (name "unconnected-(U18-GND-Pad6)") (class "Default")
      (node (ref "U18") (pin "6") (pinfunction "GND_6") (pintype "passive"))
    )
    (net (code "163") (name "unconnected-(U21-Pad1)") (class "Default")
      (node (ref "U21") (pin "1") (pinfunction "1_1") (pintype "passive"))
    )
    (net (code "164") (name "unconnected-(U21-Pad2)") (class "Default")
      (node (ref "U21") (pin "2") (pinfunction "2_2") (pintype "passive"))
    )
    (net (code "165") (name "unconnected-(U21-Pad3)") (class "Default")
      (node (ref "U21") (pin "3") (pinfunction "3_3") (pintype "passive"))
    )
    (net (code "166") (name "unconnected-(U21-Pad6)") (class "Default")
      (node (ref "U21") (pin "6") (pinfunction "6_6") (pintype "passive"))
    )
    (net (code "167") (name "unconnected-(U21-Pad7)") (class "Default")
      (node (ref "U21") (pin "7") (pinfunction "7_7") (pintype "passive"))
    )
    (net (code "168") (name "unconnected-(U21-Pad8)") (class "Default")
      (node (ref "U21") (pin "8") (pinfunction "8_8") (pintype "passive"))
    )
    (net (code "169") (name "unconnected-(U21-Pad9)") (class "Default")
      (node (ref "U21") (pin "9") (pinfunction "9_9") (pintype "passive"))
    )
    (net (code "170") (name "unconnected-(U21-Pad12)") (class "Default")
      (node (ref "U21") (pin "12") (pinfunction "12_12") (pintype "passive"))
    )
    (net (code "171") (name "unconnected-(U21-PadA2)") (class "Default")
      (node (ref "U21") (pin "A2") (pinfunction "A2_A2") (pintype "passive"))
    )
    (net (code "172") (name "unconnected-(U21-PadA3)") (class "Default")
      (node (ref "U21") (pin "A3") (pinfunction "A3_A3") (pintype "passive"))
    )
    (net (code "173") (name "unconnected-(U21-PadA4)") (class "Default")
      (node (ref "U21") (pin "A4") (pinfunction "A4_A4") (pintype "passive"))
    )
    (net (code "174") (name "unconnected-(U21-PadA5)") (class "Default")
      (node (ref "U21") (pin "A5") (pinfunction "A5_A5") (pintype "passive"))
    )
    (net (code "175") (name "unconnected-(U21-PadA6)") (class "Default")
      (node (ref "U21") (pin "A6") (pinfunction "A6_A6") (pintype "passive"))
    )
    (net (code "176") (name "unconnected-(U21-PadA7)") (class "Default")
      (node (ref "U21") (pin "A7") (pinfunction "A7_A7") (pintype "passive"))
    )
    (net (code "177") (name "unconnected-(U21-PadA8)") (class "Default")
      (node (ref "U21") (pin "A8") (pinfunction "A8_A8") (pintype "passive"))
    )
    (net (code "178") (name "unconnected-(U21-PadA9)") (class "Default")
      (node (ref "U21") (pin "A9") (pinfunction "A9_A9") (pintype "passive"))
    )
    (net (code "179") (name "unconnected-(U21-PadA10)") (class "Default")
      (node (ref "U21") (pin "A10") (pinfunction "A10_A10") (pintype "passive"))
    )
    (net (code "180") (name "unconnected-(U21-PadA11)") (class "Default")
      (node (ref "U21") (pin "A11") (pinfunction "A11_A11") (pintype "passive"))
    )
    (net (code "181") (name "unconnected-(U21-PadA12)") (class "Default")
      (node (ref "U21") (pin "A12") (pinfunction "A12_A12") (pintype "passive"))
    )
    (net (code "182") (name "unconnected-(U21-PadB2)") (class "Default")
      (node (ref "U21") (pin "B2") (pinfunction "B2_B2") (pintype "passive"))
    )
    (net (code "183") (name "unconnected-(U21-PadB4)") (class "Default")
      (node (ref "U21") (pin "B4") (pinfunction "B4_B4") (pintype "passive"))
    )
    (net (code "184") (name "unconnected-(U21-PadB5)") (class "Default")
      (node (ref "U21") (pin "B5") (pinfunction "B5_B5") (pintype "passive"))
    )
    (net (code "185") (name "unconnected-(U21-PadB6)") (class "Default")
      (node (ref "U21") (pin "B6") (pinfunction "B6_B6") (pintype "passive"))
    )
    (net (code "186") (name "unconnected-(U21-PadB7)") (class "Default")
      (node (ref "U21") (pin "B7") (pinfunction "B7_B7") (pintype "passive"))
    )
    (net (code "187") (name "unconnected-(U21-PadB9)") (class "Default")
      (node (ref "U21") (pin "B9") (pinfunction "B9_B9") (pintype "passive"))
    )
    (net (code "188") (name "unconnected-(U21-PadB10)") (class "Default")
      (node (ref "U21") (pin "B10") (pinfunction "B10_B10") (pintype "passive"))
    )
    (net (code "189") (name "unconnected-(U21-PadB11)") (class "Default")
      (node (ref "U21") (pin "B11") (pinfunction "B11_B11") (pintype "passive"))
    )
    (net (code "190") (name "unconnected-(U21-PadB12)") (class "Default")
      (node (ref "U21") (pin "B12") (pinfunction "B12_B12") (pintype "passive"))
    )
    (net (code "191") (name "unconnected-(U21-PadC4)") (class "Default")
      (node (ref "U21") (pin "C4") (pinfunction "C4_C4") (pintype "passive"))
    )
    (net (code "192") (name "unconnected-(U21-PadC5)") (class "Default")
      (node (ref "U21") (pin "C5") (pinfunction "C5_C5") (pintype "passive"))
    )
    (net (code "193") (name "unconnected-(U21-PadC6)") (class "Default")
      (node (ref "U21") (pin "C6") (pinfunction "C6_C6") (pintype "passive"))
    )
    (net (code "194") (name "unconnected-(U21-PadC7)") (class "Default")
      (node (ref "U21") (pin "C7") (pinfunction "C7_C7") (pintype "passive"))
    )
    (net (code "195") (name "unconnected-(U21-PadC9)") (class "Default")
      (node (ref "U21") (pin "C9") (pinfunction "C9_C9") (pintype "passive"))
    )
    (net (code "196") (name "unconnected-(U21-PadC11)") (class "Default")
      (node (ref "U21") (pin "C11") (pinfunction "C11_C11") (pintype "passive"))
    )
    (net (code "197") (name "unconnected-(U21-PadD5)") (class "Default")
      (node (ref "U21") (pin "D5") (pinfunction "D5_D5") (pintype "passive"))
    )
    (net (code "198") (name "unconnected-(U21-PadD6)") (class "Default")
      (node (ref "U21") (pin "D6") (pinfunction "D6_D6") (pintype "passive"))
    )
    (net (code "199") (name "unconnected-(U21-PadD7)") (class "Default")
      (node (ref "U21") (pin "D7") (pinfunction "D7_D7") (pintype "passive"))
    )
    (net (code "200") (name "unconnected-(U21-PadD10)") (class "Default")
      (node (ref "U21") (pin "D10") (pinfunction "D10_D10") (pintype "passive"))
    )
    (net (code "201") (name "unconnected-(U21-PadE5)") (class "Default")
      (node (ref "U21") (pin "E5") (pinfunction "E5_E5") (pintype "passive"))
    )
    (net (code "202") (name "unconnected-(U21-PadE6)") (class "Default")
      (node (ref "U21") (pin "E6") (pinfunction "E6_E6") (pintype "passive"))
    )
    (net (code "203") (name "unconnected-(U21-PadE7)") (class "Default")
      (node (ref "U21") (pin "E7") (pinfunction "E7_E7") (pintype "passive"))
    )
    (net (code "204") (name "unconnected-(U21-PadE10)") (class "Default")
      (node (ref "U21") (pin "E10") (pinfunction "E10_E10") (pintype "passive"))
    )
    (net (code "205") (name "unconnected-(U22-PadA1)") (class "Default")
      (node (ref "U22") (pin "A1") (pinfunction "A1_A1") (pintype "passive"))
    )
    (net (code "206") (name "unconnected-(U22-PadA2)") (class "Default")
      (node (ref "U22") (pin "A2") (pinfunction "A2_A2") (pintype "passive"))
    )
    (net (code "207") (name "unconnected-(U22-PadA3)") (class "Default")
      (node (ref "U22") (pin "A3") (pinfunction "A3_A3") (pintype "passive"))
    )
    (net (code "208") (name "unconnected-(U22-PadA4)") (class "Default")
      (node (ref "U22") (pin "A4") (pinfunction "A4_A4") (pintype "passive"))
    )
    (net (code "209") (name "unconnected-(U22-PadA5)") (class "Default")
      (node (ref "U22") (pin "A5") (pinfunction "A5_A5") (pintype "passive"))
    )
    (net (code "210") (name "unconnected-(U22-PadA6)") (class "Default")
      (node (ref "U22") (pin "A6") (pinfunction "A6_A6") (pintype "passive"))
    )
    (net (code "211") (name "unconnected-(U22-PadA7)") (class "Default")
      (node (ref "U22") (pin "A7") (pinfunction "A7_A7") (pintype "passive"))
    )
    (net (code "212") (name "unconnected-(U22-PadA8)") (class "Default")
      (node (ref "U22") (pin "A8") (pinfunction "A8_A8") (pintype "passive"))
    )
    (net (code "213") (name "unconnected-(U22-PadA9)") (class "Default")
      (node (ref "U22") (pin "A9") (pinfunction "A9_A9") (pintype "passive"))
    )
    (net (code "214") (name "unconnected-(U22-PadA10)") (class "Default")
      (node (ref "U22") (pin "A10") (pinfunction "A10_A10") (pintype "passive"))
    )
    (net (code "215") (name "unconnected-(U22-PadA11)") (class "Default")
      (node (ref "U22") (pin "A11") (pinfunction "A11_A11") (pintype "passive"))
    )
    (net (code "216") (name "unconnected-(U22-PadA12)") (class "Default")
      (node (ref "U22") (pin "A12") (pinfunction "A12_A12") (pintype "passive"))
    )
    (net (code "217") (name "unconnected-(U22-PadB1)") (class "Default")
      (node (ref "U22") (pin "B1") (pinfunction "B1_B1") (pintype "passive"))
    )
    (net (code "218") (name "unconnected-(U22-PadB2)") (class "Default")
      (node (ref "U22") (pin "B2") (pinfunction "B2_B2") (pintype "passive"))
    )
    (net (code "219") (name "unconnected-(U22-PadB3)") (class "Default")
      (node (ref "U22") (pin "B3") (pinfunction "B3_B3") (pintype "passive"))
    )
    (net (code "220") (name "unconnected-(U22-PadB4)") (class "Default")
      (node (ref "U22") (pin "B4") (pinfunction "B4_B4") (pintype "passive"))
    )
    (net (code "221") (name "unconnected-(U22-PadB5)") (class "Default")
      (node (ref "U22") (pin "B5") (pinfunction "B5_B5") (pintype "passive"))
    )
    (net (code "222") (name "unconnected-(U22-PadB6)") (class "Default")
      (node (ref "U22") (pin "B6") (pinfunction "B6_B6") (pintype "passive"))
    )
    (net (code "223") (name "unconnected-(U22-PadB7)") (class "Default")
      (node (ref "U22") (pin "B7") (pinfunction "B7_B7") (pintype "passive"))
    )
    (net (code "224") (name "unconnected-(U22-PadB8)") (class "Default")
      (node (ref "U22") (pin "B8") (pinfunction "B8_B8") (pintype "passive"))
    )
    (net (code "225") (name "unconnected-(U22-PadB9)") (class "Default")
      (node (ref "U22") (pin "B9") (pinfunction "B9_B9") (pintype "passive"))
    )
    (net (code "226") (name "unconnected-(U22-PadB10)") (class "Default")
      (node (ref "U22") (pin "B10") (pinfunction "B10_B10") (pintype "passive"))
    )
    (net (code "227") (name "unconnected-(U22-PadB11)") (class "Default")
      (node (ref "U22") (pin "B11") (pinfunction "B11_B11") (pintype "passive"))
    )
    (net (code "228") (name "unconnected-(U22-PadB12)") (class "Default")
      (node (ref "U22") (pin "B12") (pinfunction "B12_B12") (pintype "passive"))
    )
    (net (code "229") (name "unconnected-(U22-PadC1)") (class "Default")
      (node (ref "U22") (pin "C1") (pinfunction "C1_C1") (pintype "passive"))
    )
    (net (code "230") (name "unconnected-(U22-PadC2)") (class "Default")
      (node (ref "U22") (pin "C2") (pinfunction "C2_C2") (pintype "passive"))
    )
    (net (code "231") (name "unconnected-(U22-PadC3)") (class "Default")
      (node (ref "U22") (pin "C3") (pinfunction "C3_C3") (pintype "passive"))
    )
    (net (code "232") (name "unconnected-(U22-PadC4)") (class "Default")
      (node (ref "U22") (pin "C4") (pinfunction "C4_C4") (pintype "passive"))
    )
    (net (code "233") (name "unconnected-(U22-PadC5)") (class "Default")
      (node (ref "U22") (pin "C5") (pinfunction "C5_C5") (pintype "passive"))
    )
    (net (code "234") (name "unconnected-(U22-PadC6)") (class "Default")
      (node (ref "U22") (pin "C6") (pinfunction "C6_C6") (pintype "passive"))
    )
    (net (code "235") (name "unconnected-(U22-PadC7)") (class "Default")
      (node (ref "U22") (pin "C7") (pinfunction "C7_C7") (pintype "passive"))
    )
    (net (code "236") (name "unconnected-(U22-PadC8)") (class "Default")
      (node (ref "U22") (pin "C8") (pinfunction "C8_C8") (pintype "passive"))
    )
    (net (code "237") (name "unconnected-(U22-PadC9)") (class "Default")
      (node (ref "U22") (pin "C9") (pinfunction "C9_C9") (pintype "passive"))
    )
    (net (code "238") (name "unconnected-(U22-PadC10)") (class "Default")
      (node (ref "U22") (pin "C10") (pinfunction "C10_C10") (pintype "passive"))
    )
    (net (code "239") (name "unconnected-(U22-PadC11)") (class "Default")
      (node (ref "U22") (pin "C11") (pinfunction "C11_C11") (pintype "passive"))
    )
    (net (code "240") (name "unconnected-(U22-PadC12)") (class "Default")
      (node (ref "U22") (pin "C12") (pinfunction "C12_C12") (pintype "passive"))
    )
    (net (code "241") (name "unconnected-(U22-PadD1)") (class "Default")
      (node (ref "U22") (pin "D1") (pinfunction "D1_D1") (pintype "passive"))
    )
    (net (code "242") (name "unconnected-(U22-PadD2)") (class "Default")
      (node (ref "U22") (pin "D2") (pinfunction "D2_D2") (pintype "passive"))
    )
    (net (code "243") (name "unconnected-(U22-PadD3)") (class "Default")
      (node (ref "U22") (pin "D3") (pinfunction "D3_D3") (pintype "passive"))
    )
    (net (code "244") (name "unconnected-(U22-PadD4)") (class "Default")
      (node (ref "U22") (pin "D4") (pinfunction "D4_D4") (pintype "passive"))
    )
    (net (code "245") (name "unconnected-(U22-PadD5)") (class "Default")
      (node (ref "U22") (pin "D5") (pinfunction "D5_D5") (pintype "passive"))
    )
    (net (code "246") (name "unconnected-(U22-PadD6)") (class "Default")
      (node (ref "U22") (pin "D6") (pinfunction "D6_D6") (pintype "passive"))
    )
    (net (code "247") (name "unconnected-(U22-PadD7)") (class "Default")
      (node (ref "U22") (pin "D7") (pinfunction "D7_D7") (pintype "passive"))
    )
    (net (code "248") (name "unconnected-(U22-PadD8)") (class "Default")
      (node (ref "U22") (pin "D8") (pinfunction "D8_D8") (pintype "passive"))
    )
    (net (code "249") (name "unconnected-(U22-PadD9)") (class "Default")
      (node (ref "U22") (pin "D9") (pinfunction "D9_D9") (pintype "passive"))
    )
    (net (code "250") (name "unconnected-(U22-PadD10)") (class "Default")
      (node (ref "U22") (pin "D10") (pinfunction "D10_D10") (pintype "passive"))
    )
    (net (code "251") (name "unconnected-(U22-PadD11)") (class "Default")
      (node (ref "U22") (pin "D11") (pinfunction "D11_D11") (pintype "passive"))
    )
    (net (code "252") (name "unconnected-(U22-PadD12)") (class "Default")
      (node (ref "U22") (pin "D12") (pinfunction "D12_D12") (pintype "passive"))
    )
    (net (code "253") (name "unconnected-(U22-PadE1)") (class "Default")
      (node (ref "U22") (pin "E1") (pinfunction "E1_E1") (pintype "passive"))
    )
    (net (code "254") (name "unconnected-(U22-PadE2)") (class "Default")
      (node (ref "U22") (pin "E2") (pinfunction "E2_E2") (pintype "passive"))
    )
    (net (code "255") (name "unconnected-(U22-PadE3)") (class "Default")
      (node (ref "U22") (pin "E3") (pinfunction "E3_E3") (pintype "passive"))
    )
    (net (code "256") (name "unconnected-(U22-PadE4)") (class "Default")
      (node (ref "U22") (pin "E4") (pinfunction "E4_E4") (pintype "passive"))
    )
    (net (code "257") (name "unconnected-(U22-PadE5)") (class "Default")
      (node (ref "U22") (pin "E5") (pinfunction "E5_E5") (pintype "passive"))
    )
    (net (code "258") (name "unconnected-(U22-PadE6)") (class "Default")
      (node (ref "U22") (pin "E6") (pinfunction "E6_E6") (pintype "passive"))
    )
    (net (code "259") (name "unconnected-(U22-PadE7)") (class "Default")
      (node (ref "U22") (pin "E7") (pinfunction "E7_E7") (pintype "passive"))
    )
    (net (code "260") (name "unconnected-(U22-PadE8)") (class "Default")
      (node (ref "U22") (pin "E8") (pinfunction "E8_E8") (pintype "passive"))
    )
    (net (code "261") (name "unconnected-(U22-PadE9)") (class "Default")
      (node (ref "U22") (pin "E9") (pinfunction "E9_E9") (pintype "passive"))
    )
    (net (code "262") (name "unconnected-(U22-PadE10)") (class "Default")
      (node (ref "U22") (pin "E10") (pinfunction "E10_E10") (pintype "passive"))
    )
    (net (code "263") (name "unconnected-(U22-PadE11)") (class "Default")
      (node (ref "U22") (pin "E11") (pinfunction "E11_E11") (pintype "passive"))
    )
    (net (code "264") (name "unconnected-(U22-PadE12)") (class "Default")
      (node (ref "U22") (pin "E12") (pinfunction "E12_E12") (pintype "passive"))
    )
  )
)
